# GWLSensorv8.net
KiCad netlist of a schematic drawn in EAGLE
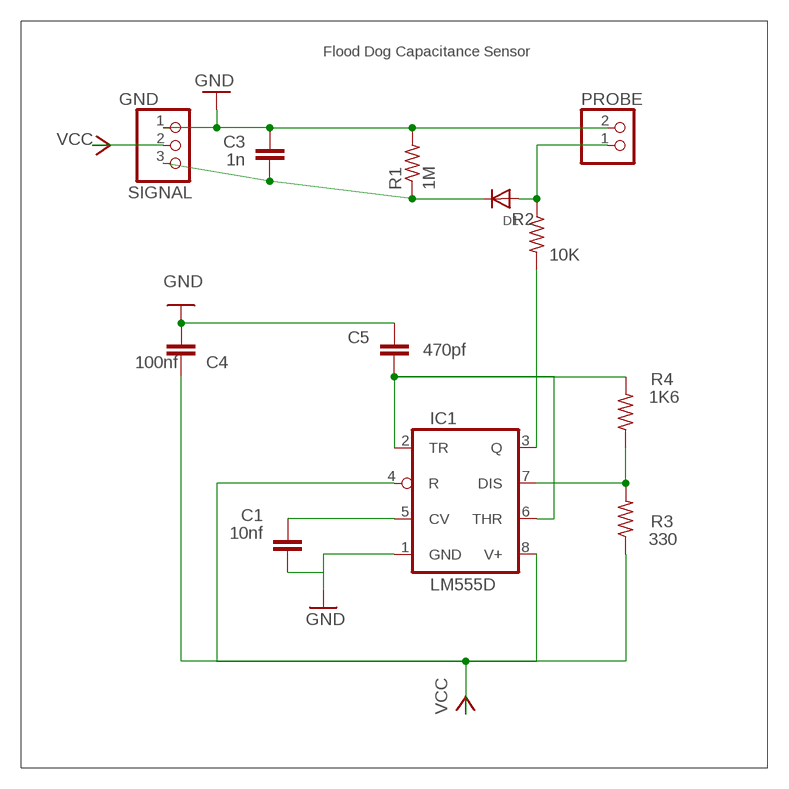
[diagram p0: schematic, sheet 1]

(export (version "E")
  (design (tool "Eeschema 10.0.6"))
  (components
    (comp (ref "C1")
      (value "10nf")
      (footprint "eagle-import:C0805")
      (libsource (lib "eagle-import") (part "C-EUC0805"))
    )
    (comp (ref "C3")
      (value "1n")
      (footprint "eagle-import:C0805")
      (libsource (lib "eagle-import") (part "C-EUC0805"))
    )
    (comp (ref "C4")
      (value "100nf")
      (footprint "eagle-import:C0805")
      (libsource (lib "eagle-import") (part "C-EUC0805"))
    )
    (comp (ref "C5")
      (value "470pf")
      (footprint "eagle-import:C0805")
      (libsource (lib "eagle-import") (part "C-EUC0805"))
    )
    (comp (ref "D1")
      (value "DIODESMA")
      (footprint "eagle-import:SMADIODE")
      (libsource (lib "eagle-import") (part "DIODESMA"))
    )
    (comp (ref "GND")
      (value "JST_3PIN")
      (footprint "eagle-import:JSTPH3")
      (libsource (lib "eagle-import") (part "JST_3PIN"))
    )
    (comp (ref "IC1")
      (value "LM555D")
      (footprint "eagle-import:SO08")
      (libsource (lib "eagle-import") (part "555DLM"))
    )
    (comp (ref "PROBE")
      (value "JST_2PIN-SMT")
      (footprint "eagle-import:JST-PH-2-SMT")
      (libsource (lib "eagle-import") (part "JST_2PIN-SMT"))
    )
    (comp (ref "R1")
      (value "1M")
      (footprint "eagle-import:R0805")
      (libsource (lib "eagle-import") (part "R-US_R0805"))
    )
    (comp (ref "R2")
      (value "10K")
      (footprint "eagle-import:R0805")
      (libsource (lib "eagle-import") (part "R-US_R0805"))
    )
    (comp (ref "R3")
      (value "330")
      (footprint "eagle-import:R0805")
      (libsource (lib "eagle-import") (part "R-US_R0805"))
    )
    (comp (ref "R4")
      (value "1K6")
      (footprint "eagle-import:R0805")
      (libsource (lib "eagle-import") (part "R-US_R0805"))
    )
  )
  (nets
    (net (code "1") (name "/SIGNAL") (class "Default")
      (node (ref "C3") (pin "1") (pinfunction "1_1") (pintype "passive"))
      (node (ref "D1") (pin "C") (pinfunction "C_C") (pintype "passive"))
      (node (ref "GND") (pin "3") (pinfunction "3_3") (pintype "passive"))
      (node (ref "R1") (pin "1") (pinfunction "1_1") (pintype "passive"))
    )
    (net (code "2") (name "GND") (class "Default")
      (node (ref "C1") (pin "1") (pinfunction "1_1") (pintype "passive"))
      (node (ref "C3") (pin "2") (pinfunction "2_2") (pintype "passive"))
      (node (ref "C4") (pin "1") (pinfunction "1_1") (pintype "passive"))
      (node (ref "C5") (pin "2") (pinfunction "2_2") (pintype "passive"))
      (node (ref "GND") (pin "1") (pinfunction "1_1") (pintype "passive"))
      (node (ref "IC1") (pin "1") (pinfunction "GND_1") (pintype "power_in"))
      (node (ref "PROBE") (pin "2") (pinfunction "1_2") (pintype "passive"))
      (node (ref "R1") (pin "2") (pinfunction "2_2") (pintype "passive"))
    )
    (net (code "3") (name "Net-(IC1-CV)") (class "Default")
      (node (ref "C1") (pin "2") (pinfunction "2_2") (pintype "passive"))
      (node (ref "IC1") (pin "5") (pinfunction "CV_5") (pintype "input"))
    )
    (net (code "4") (name "Net-(IC1-DIS)") (class "Default")
      (node (ref "IC1") (pin "7") (pinfunction "DIS_7") (pintype "input"))
      (node (ref "R3") (pin "2") (pinfunction "2_2") (pintype "passive"))
      (node (ref "R4") (pin "1") (pinfunction "1_1") (pintype "passive"))
    )
    (net (code "5") (name "Net-(IC1-Q)") (class "Default")
      (node (ref "IC1") (pin "3") (pinfunction "Q_3") (pintype "output"))
      (node (ref "R2") (pin "2") (pinfunction "2_2") (pintype "passive"))
    )
    (net (code "6") (name "Net-(IC1-THR)") (class "Default")
      (node (ref "C5") (pin "1") (pinfunction "1_1") (pintype "passive"))
      (node (ref "IC1") (pin "2") (pinfunction "TR_2") (pintype "input"))
      (node (ref "IC1") (pin "6") (pinfunction "THR_6") (pintype "input"))
      (node (ref "R4") (pin "2") (pinfunction "2_2") (pintype "passive"))
    )
    (net (code "7") (name "Net-(PROBE-2)") (class "Default")
      (node (ref "D1") (pin "A") (pinfunction "A_A") (pintype "passive"))
      (node (ref "PROBE") (pin "1") (pinfunction "2_1") (pintype "passive"))
      (node (ref "R2") (pin "1") (pinfunction "1_1") (pintype "passive"))
    )
    (net (code "8") (name "VCC") (class "Default")
      (node (ref "C4") (pin "2") (pinfunction "2_2") (pintype "passive"))
      (node (ref "GND") (pin "2") (pinfunction "2_2") (pintype "passive"))
      (node (ref "IC1") (pin "4") (pinfunction "R_4") (pintype "input"))
      (node (ref "IC1") (pin "8") (pinfunction "V+_8") (pintype "power_in"))
      (node (ref "R3") (pin "1") (pinfunction "1_1") (pintype "passive"))
    )
  )
)
